# Below_IR_Matrix.net
KiCad netlist of a schematic drawn in EAGLE
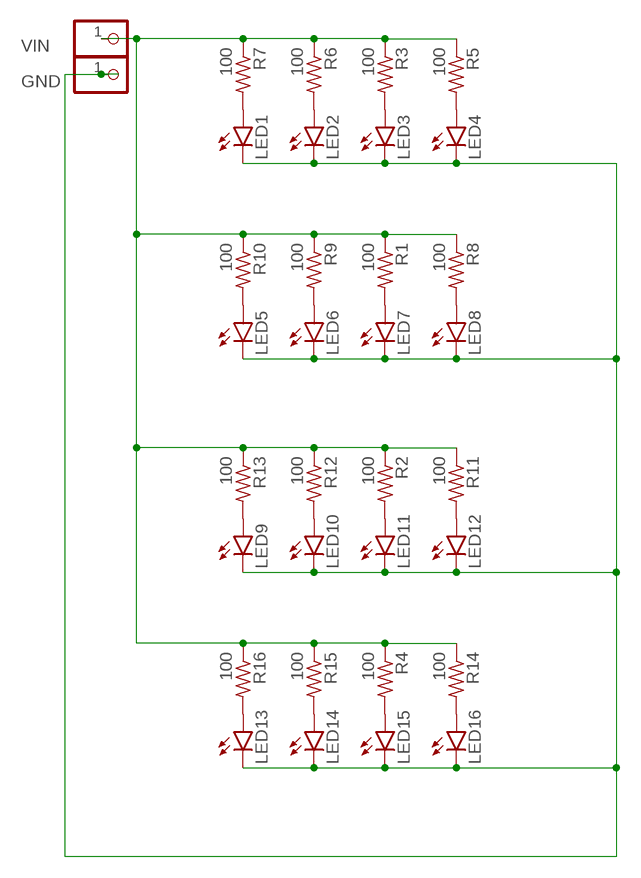
[diagram p0: schematic, sheet 1]

(export (version "E")
  (design (tool "Eeschema 10.0.6"))
  (components
    (comp (ref "GND")
      (value "PINHD-1X1")
      (footprint "eagle-import:1X01")
      (libsource (lib "eagle-import") (part "PINHD-1X1"))
    )
    (comp (ref "LED1")
      (value "LED5MM")
      (footprint "eagle-import:LED5MM")
      (libsource (lib "eagle-import") (part "LED5MM"))
    )
    (comp (ref "LED2")
      (value "LED5MM")
      (footprint "eagle-import:LED5MM")
      (libsource (lib "eagle-import") (part "LED5MM"))
    )
    (comp (ref "LED3")
      (value "LED5MM")
      (footprint "eagle-import:LED5MM")
      (libsource (lib "eagle-import") (part "LED5MM"))
    )
    (comp (ref "LED4")
      (value "LED5MM")
      (footprint "eagle-import:LED5MM")
      (libsource (lib "eagle-import") (part "LED5MM"))
    )
    (comp (ref "LED5")
      (value "LED5MM")
      (footprint "eagle-import:LED5MM")
      (libsource (lib "eagle-import") (part "LED5MM"))
    )
    (comp (ref "LED6")
      (value "LED5MM")
      (footprint "eagle-import:LED5MM")
      (libsource (lib "eagle-import") (part "LED5MM"))
    )
    (comp (ref "LED7")
      (value "LED5MM")
      (footprint "eagle-import:LED5MM")
      (libsource (lib "eagle-import") (part "LED5MM"))
    )
    (comp (ref "LED8")
      (value "LED5MM")
      (footprint "eagle-import:LED5MM")
      (libsource (lib "eagle-import") (part "LED5MM"))
    )
    (comp (ref "LED9")
      (value "LED5MM")
      (footprint "eagle-import:LED5MM")
      (libsource (lib "eagle-import") (part "LED5MM"))
    )
    (comp (ref "LED10")
      (value "LED5MM")
      (footprint "eagle-import:LED5MM")
      (libsource (lib "eagle-import") (part "LED5MM"))
    )
    (comp (ref "LED11")
      (value "LED5MM")
      (footprint "eagle-import:LED5MM")
      (libsource (lib "eagle-import") (part "LED5MM"))
    )
    (comp (ref "LED12")
      (value "LED5MM")
      (footprint "eagle-import:LED5MM")
      (libsource (lib "eagle-import") (part "LED5MM"))
    )
    (comp (ref "LED13")
      (value "LED5MM")
      (footprint "eagle-import:LED5MM")
      (libsource (lib "eagle-import") (part "LED5MM"))
    )
    (comp (ref "LED14")
      (value "LED5MM")
      (footprint "eagle-import:LED5MM")
      (libsource (lib "eagle-import") (part "LED5MM"))
    )
    (comp (ref "LED15")
      (value "LED5MM")
      (footprint "eagle-import:LED5MM")
      (libsource (lib "eagle-import") (part "LED5MM"))
    )
    (comp (ref "LED16")
      (value "LED5MM")
      (footprint "eagle-import:LED5MM")
      (libsource (lib "eagle-import") (part "LED5MM"))
    )
    (comp (ref "R1")
      (value "100")
      (footprint "eagle-import:0207_10")
      (libsource (lib "eagle-import") (part "R-US_0207/10"))
    )
    (comp (ref "R2")
      (value "100")
      (footprint "eagle-import:0207_10")
      (libsource (lib "eagle-import") (part "R-US_0207/10"))
    )
    (comp (ref "R3")
      (value "100")
      (footprint "eagle-import:0207_10")
      (libsource (lib "eagle-import") (part "R-US_0207/10"))
    )
    (comp (ref "R4")
      (value "100")
      (footprint "eagle-import:0207_10")
      (libsource (lib "eagle-import") (part "R-US_0207/10"))
    )
    (comp (ref "R5")
      (value "100")
      (footprint "eagle-import:0207_10")
      (libsource (lib "eagle-import") (part "R-US_0207/10"))
    )
    (comp (ref "R6")
      (value "100")
      (footprint "eagle-import:0207_10")
      (libsource (lib "eagle-import") (part "R-US_0207/10"))
    )
    (comp (ref "R7")
      (value "100")
      (footprint "eagle-import:0207_10")
      (libsource (lib "eagle-import") (part "R-US_0207/10"))
    )
    (comp (ref "R8")
      (value "100")
      (footprint "eagle-import:0207_10")
      (libsource (lib "eagle-import") (part "R-US_0207/10"))
    )
    (comp (ref "R9")
      (value "100")
      (footprint "eagle-import:0207_10")
      (libsource (lib "eagle-import") (part "R-US_0207/10"))
    )
    (comp (ref "R10")
      (value "100")
      (footprint "eagle-import:0207_10")
      (libsource (lib "eagle-import") (part "R-US_0207/10"))
    )
    (comp (ref "R11")
      (value "100")
      (footprint "eagle-import:0207_10")
      (libsource (lib "eagle-import") (part "R-US_0207/10"))
    )
    (comp (ref "R12")
      (value "100")
      (footprint "eagle-import:0207_10")
      (libsource (lib "eagle-import") (part "R-US_0207/10"))
    )
    (comp (ref "R13")
      (value "100")
      (footprint "eagle-import:0207_10")
      (libsource (lib "eagle-import") (part "R-US_0207/10"))
    )
    (comp (ref "R14")
      (value "100")
      (footprint "eagle-import:0207_10")
      (libsource (lib "eagle-import") (part "R-US_0207/10"))
    )
    (comp (ref "R15")
      (value "100")
      (footprint "eagle-import:0207_10")
      (libsource (lib "eagle-import") (part "R-US_0207/10"))
    )
    (comp (ref "R16")
      (value "100")
      (footprint "eagle-import:0207_10")
      (libsource (lib "eagle-import") (part "R-US_0207/10"))
    )
    (comp (ref "VIN")
      (value "PINHD-1X1")
      (footprint "eagle-import:1X01")
      (libsource (lib "eagle-import") (part "PINHD-1X1"))
    )
  )
  (nets
    (net (code "1") (name "Net-(LED1-C)") (class "Default")
      (node (ref "GND") (pin "1") (pinfunction "1_1") (pintype "passive"))
      (node (ref "LED1") (pin "K") (pinfunction "C_K") (pintype "passive"))
      (node (ref "LED10") (pin "K") (pinfunction "C_K") (pintype "passive"))
      (node (ref "LED11") (pin "K") (pinfunction "C_K") (pintype "passive"))
      (node (ref "LED12") (pin "K") (pinfunction "C_K") (pintype "passive"))
      (node (ref "LED13") (pin "K") (pinfunction "C_K") (pintype "passive"))
      (node (ref "LED14") (pin "K") (pinfunction "C_K") (pintype "passive"))
      (node (ref "LED15") (pin "K") (pinfunction "C_K") (pintype "passive"))
      (node (ref "LED16") (pin "K") (pinfunction "C_K") (pintype "passive"))
      (node (ref "LED2") (pin "K") (pinfunction "C_K") (pintype "passive"))
      (node (ref "LED3") (pin "K") (pinfunction "C_K") (pintype "passive"))
      (node (ref "LED4") (pin "K") (pinfunction "C_K") (pintype "passive"))
      (node (ref "LED5") (pin "K") (pinfunction "C_K") (pintype "passive"))
      (node (ref "LED6") (pin "K") (pinfunction "C_K") (pintype "passive"))
      (node (ref "LED7") (pin "K") (pinfunction "C_K") (pintype "passive"))
      (node (ref "LED8") (pin "K") (pinfunction "C_K") (pintype "passive"))
      (node (ref "LED9") (pin "K") (pinfunction "C_K") (pintype "passive"))
    )
    (net (code "2") (name "Net-(LED1-PadA)") (class "Default")
      (node (ref "LED1") (pin "A") (pinfunction "A_A") (pintype "passive"))
      (node (ref "R7") (pin "2") (pinfunction "2_2") (pintype "passive"))
    )
    (net (code "3") (name "Net-(LED2-PadA)") (class "Default")
      (node (ref "LED2") (pin "A") (pinfunction "A_A") (pintype "passive"))
      (node (ref "R6") (pin "2") (pinfunction "2_2") (pintype "passive"))
    )
    (net (code "4") (name "Net-(LED3-PadA)") (class "Default")
      (node (ref "LED3") (pin "A") (pinfunction "A_A") (pintype "passive"))
      (node (ref "R3") (pin "2") (pinfunction "2_2") (pintype "passive"))
    )
    (net (code "5") (name "Net-(LED4-PadA)") (class "Default")
      (node (ref "LED4") (pin "A") (pinfunction "A_A") (pintype "passive"))
      (node (ref "R5") (pin "2") (pinfunction "2_2") (pintype "passive"))
    )
    (net (code "6") (name "Net-(LED5-PadA)") (class "Default")
      (node (ref "LED5") (pin "A") (pinfunction "A_A") (pintype "passive"))
      (node (ref "R10") (pin "2") (pinfunction "2_2") (pintype "passive"))
    )
    (net (code "7") (name "Net-(LED6-PadA)") (class "Default")
      (node (ref "LED6") (pin "A") (pinfunction "A_A") (pintype "passive"))
      (node (ref "R9") (pin "2") (pinfunction "2_2") (pintype "passive"))
    )
    (net (code "8") (name "Net-(LED7-PadA)") (class "Default")
      (node (ref "LED7") (pin "A") (pinfunction "A_A") (pintype "passive"))
      (node (ref "R1") (pin "2") (pinfunction "2_2") (pintype "passive"))
    )
    (net (code "9") (name "Net-(LED8-PadA)") (class "Default")
      (node (ref "LED8") (pin "A") (pinfunction "A_A") (pintype "passive"))
      (node (ref "R8") (pin "2") (pinfunction "2_2") (pintype "passive"))
    )
    (net (code "10") (name "Net-(LED9-PadA)") (class "Default")
      (node (ref "LED9") (pin "A") (pinfunction "A_A") (pintype "passive"))
      (node (ref "R13") (pin "2") (pinfunction "2_2") (pintype "passive"))
    )
    (net (code "11") (name "Net-(LED10-PadA)") (class "Default")
      (node (ref "LED10") (pin "A") (pinfunction "A_A") (pintype "passive"))
      (node (ref "R12") (pin "2") (pinfunction "2_2") (pintype "passive"))
    )
    (net (code "12") (name "Net-(LED11-PadA)") (class "Default")
      (node (ref "LED11") (pin "A") (pinfunction "A_A") (pintype "passive"))
      (node (ref "R2") (pin "2") (pinfunction "2_2") (pintype "passive"))
    )
    (net (code "13") (name "Net-(LED12-PadA)") (class "Default")
      (node (ref "LED12") (pin "A") (pinfunction "A_A") (pintype "passive"))
      (node (ref "R11") (pin "2") (pinfunction "2_2") (pintype "passive"))
    )
    (net (code "14") (name "Net-(LED13-PadA)") (class "Default")
      (node (ref "LED13") (pin "A") (pinfunction "A_A") (pintype "passive"))
      (node (ref "R16") (pin "2") (pinfunction "2_2") (pintype "passive"))
    )
    (net (code "15") (name "Net-(LED14-PadA)") (class "Default")
      (node (ref "LED14") (pin "A") (pinfunction "A_A") (pintype "passive"))
      (node (ref "R15") (pin "2") (pinfunction "2_2") (pintype "passive"))
    )
    (net (code "16") (name "Net-(LED15-PadA)") (class "Default")
      (node (ref "LED15") (pin "A") (pinfunction "A_A") (pintype "passive"))
      (node (ref "R4") (pin "2") (pinfunction "2_2") (pintype "passive"))
    )
    (net (code "17") (name "Net-(LED16-PadA)") (class "Default")
      (node (ref "LED16") (pin "A") (pinfunction "A_A") (pintype "passive"))
      (node (ref "R14") (pin "2") (pinfunction "2_2") (pintype "passive"))
    )
    (net (code "18") (name "Net-(R1-Pad1)") (class "Default")
      (node (ref "R1") (pin "1") (pinfunction "1_1") (pintype "passive"))
      (node (ref "R10") (pin "1") (pinfunction "1_1") (pintype "passive"))
      (node (ref "R11") (pin "1") (pinfunction "1_1") (pintype "passive"))
      (node (ref "R12") (pin "1") (pinfunction "1_1") (pintype "passive"))
      (node (ref "R13") (pin "1") (pinfunction "1_1") (pintype "passive"))
      (node (ref "R14") (pin "1") (pinfunction "1_1") (pintype "passive"))
      (node (ref "R15") (pin "1") (pinfunction "1_1") (pintype "passive"))
      (node (ref "R16") (pin "1") (pinfunction "1_1") (pintype "passive"))
      (node (ref "R2") (pin "1") (pinfunction "1_1") (pintype "passive"))
      (node (ref "R3") (pin "1") (pinfunction "1_1") (pintype "passive"))
      (node (ref "R4") (pin "1") (pinfunction "1_1") (pintype "passive"))
      (node (ref "R5") (pin "1") (pinfunction "1_1") (pintype "passive"))
      (node (ref "R6") (pin "1") (pinfunction "1_1") (pintype "passive"))
      (node (ref "R7") (pin "1") (pinfunction "1_1") (pintype "passive"))
      (node (ref "R8") (pin "1") (pinfunction "1_1") (pintype "passive"))
      (node (ref "R9") (pin "1") (pinfunction "1_1") (pintype "passive"))
      (node (ref "VIN") (pin "1") (pinfunction "1_1") (pintype "passive"))
    )
  )
)
